# 1DPong_FootController.net
KiCad netlist of a schematic drawn in EAGLE
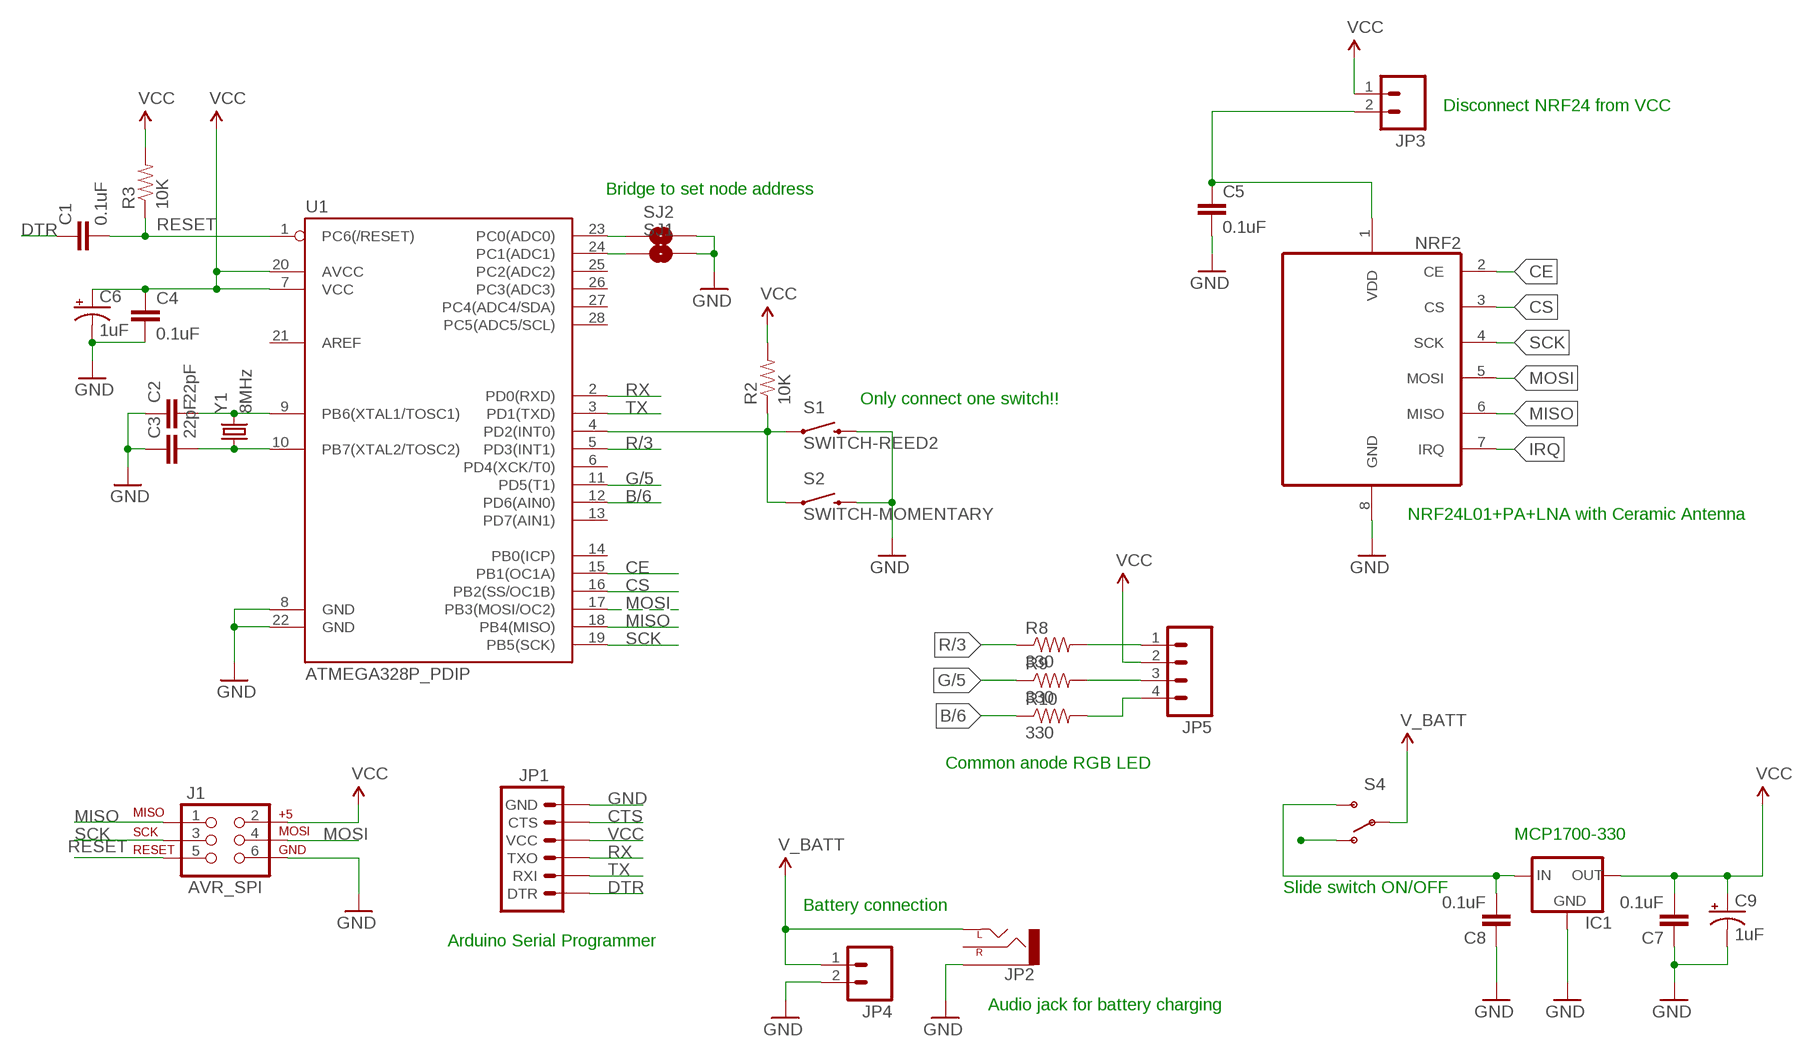
[diagram p0: schematic, sheet 1]

(export (version "E")
  (design (tool "Eeschema 10.0.6"))
  (components
    (comp (ref "C1")
      (value "0.1uF")
      (footprint "eagle-import:CAP-PTH-SMALL")
      (libsource (lib "eagle-import") (part "CAPPTH"))
    )
    (comp (ref "C2")
      (value "22pF")
      (footprint "eagle-import:CAP-PTH-SMALL")
      (libsource (lib "eagle-import") (part "CAPPTH"))
    )
    (comp (ref "C3")
      (value "22pF")
      (footprint "eagle-import:CAP-PTH-SMALL")
      (libsource (lib "eagle-import") (part "CAPPTH"))
    )
    (comp (ref "C4")
      (value "0.1uF")
      (footprint "eagle-import:CAP-PTH-SMALL")
      (libsource (lib "eagle-import") (part "CAPPTH"))
    )
    (comp (ref "C5")
      (value "0.1uF")
      (footprint "eagle-import:CAP-PTH-SMALL")
      (libsource (lib "eagle-import") (part "CAPPTH"))
    )
    (comp (ref "C6")
      (value "1uF")
      (footprint "eagle-import:CPOL-RADIAL-10UF-25V")
      (libsource (lib "eagle-import") (part "CAP_POLPTH2"))
    )
    (comp (ref "C7")
      (value "0.1uF")
      (footprint "eagle-import:CAP-PTH-SMALL")
      (libsource (lib "eagle-import") (part "CAPPTH"))
    )
    (comp (ref "C8")
      (value "0.1uF")
      (footprint "eagle-import:CAP-PTH-SMALL")
      (libsource (lib "eagle-import") (part "CAPPTH"))
    )
    (comp (ref "C9")
      (value "1uF")
      (footprint "eagle-import:CPOL-RADIAL-10UF-25V")
      (libsource (lib "eagle-import") (part "CAP_POLPTH2"))
    )
    (comp (ref "IC1")
      (value "V_REG_78XXTO-92_UNTESTED")
      (footprint "eagle-import:TO-92")
      (libsource (lib "eagle-import") (part "V_REG_78XXTO-92_UNTESTED"))
    )
    (comp (ref "J1")
      (value "AVR_SPI")
      (footprint "eagle-import:2X3")
      (libsource (lib "eagle-import") (part "AVR_SPI_PRG_6PTH"))
    )
    (comp (ref "JP1")
      (value "ARDUINO_SERIAL_PROGRAMPTH")
      (footprint "eagle-import:1X06")
      (libsource (lib "eagle-import") (part "ARDUINO_SERIAL_PROGRAMPTH"))
    )
    (comp (ref "JP2")
      (value "AUDIO-JACKPTH")
      (footprint "eagle-import:AUDIO-JACK")
      (libsource (lib "eagle-import") (part "AUDIO-JACKPTH"))
    )
    (comp (ref "JP3")
      (value "M02PTH")
      (footprint "eagle-import:1X02")
      (libsource (lib "eagle-import") (part "M02PTH"))
    )
    (comp (ref "JP4")
      (value "M02PTH")
      (footprint "eagle-import:1X02")
      (libsource (lib "eagle-import") (part "M02PTH"))
    )
    (comp (ref "JP5")
      (value "M04PTH")
      (footprint "eagle-import:1X04")
      (libsource (lib "eagle-import") (part "M04PTH"))
    )
    (comp (ref "NRF2")
      (value "NRF24L01_SOIC")
      (footprint "eagle-import:NRF24L01_SOIC")
      (libsource (lib "eagle-import") (part "NRF24L01_SOIC"))
    )
    (comp (ref "R2")
      (value "10K")
      (footprint "eagle-import:1206")
      (libsource (lib "eagle-import") (part "RESISTOR1206"))
    )
    (comp (ref "R3")
      (value "10K")
      (footprint "eagle-import:1206")
      (libsource (lib "eagle-import") (part "RESISTOR1206"))
    )
    (comp (ref "R8")
      (value "330")
      (footprint "eagle-import:1206")
      (libsource (lib "eagle-import") (part "RESISTOR1206"))
    )
    (comp (ref "R9")
      (value "330")
      (footprint "eagle-import:1206")
      (libsource (lib "eagle-import") (part "RESISTOR1206"))
    )
    (comp (ref "R10")
      (value "330")
      (footprint "eagle-import:1206")
      (libsource (lib "eagle-import") (part "RESISTOR1206"))
    )
    (comp (ref "S1")
      (value "SWITCH-REED2")
      (footprint "eagle-import:REED_SWITCH_PLASTIC")
      (libsource (lib "eagle-import") (part "SWITCH-MOMENTARY-2PTH_REED2"))
    )
    (comp (ref "S2")
      (value "SWITCH-MOMENTARY")
      (footprint "eagle-import:TACTILE-PTH")
      (libsource (lib "eagle-import") (part "SWITCH-MOMENTARY-2PTH"))
    )
    (comp (ref "S4")
      (value "SWITCH-SPDT-SMD-A")
      (footprint "eagle-import:SWITCH-SPST-SMD-A")
      (libsource (lib "eagle-import") (part "SWITCH-SPDT-SMD-A"))
    )
    (comp (ref "SJ1")
      (value "JUMPER-PAD-2-NOYES_SILK")
      (footprint "eagle-import:PAD-JUMPER-2-NO_YES_SILK")
      (libsource (lib "eagle-import") (part "JUMPER-PAD-2-NOYES_SILK"))
    )
    (comp (ref "SJ2")
      (value "JUMPER-PAD-2-NOYES_SILK")
      (footprint "eagle-import:PAD-JUMPER-2-NO_YES_SILK")
      (libsource (lib "eagle-import") (part "JUMPER-PAD-2-NOYES_SILK"))
    )
    (comp (ref "U1")
      (value "ATMEGA328P_PDIP")
      (footprint "eagle-import:DIL28-3")
      (libsource (lib "eagle-import") (part "ATMEGA328P_PDIP"))
    )
    (comp (ref "Y1")
      (value "8MHz")
      (footprint "eagle-import:HC49US")
      (libsource (lib "eagle-import") (part "CRYSTALHC49US"))
    )
  )
  (nets
    (net (code "1") (name "/CTS") (class "Default")
      (node (ref "JP1") (pin "CTS") (pinfunction "CTS_CTS") (pintype "passive"))
    )
    (net (code "2") (name "/DTR") (class "Default")
      (node (ref "C1") (pin "1") (pinfunction "1_1") (pintype "passive"))
      (node (ref "JP1") (pin "DTR") (pinfunction "DTR_DTR") (pintype "passive"))
    )
    (net (code "3") (name "/RESET") (class "Default")
      (node (ref "C1") (pin "2") (pinfunction "2_2") (pintype "passive"))
      (node (ref "J1") (pin "5") (pinfunction "5_5") (pintype "passive"))
      (node (ref "R3") (pin "1") (pinfunction "1_1") (pintype "passive"))
      (node (ref "U1") (pin "1") (pinfunction "PC6(/RESET)_1") (pintype "bidirectional"))
    )
    (net (code "4") (name "/RX") (class "Default")
      (node (ref "JP1") (pin "TXO") (pinfunction "TXO_TXO") (pintype "passive"))
      (node (ref "U1") (pin "2") (pinfunction "PD0(RXD)_2") (pintype "bidirectional"))
    )
    (net (code "5") (name "/TX") (class "Default")
      (node (ref "JP1") (pin "RXI") (pinfunction "RXI_RXI") (pintype "passive"))
      (node (ref "U1") (pin "3") (pinfunction "PD1(TXD)_3") (pintype "bidirectional"))
    )
    (net (code "6") (name "B{slash}6") (class "Default")
      (node (ref "R10") (pin "1") (pinfunction "1_1") (pintype "passive"))
      (node (ref "U1") (pin "12") (pinfunction "PD6(AIN0)_12") (pintype "bidirectional"))
    )
    (net (code "7") (name "CE") (class "Default")
      (node (ref "NRF2") (pin "2") (pinfunction "CE_2") (pintype "bidirectional"))
      (node (ref "U1") (pin "15") (pinfunction "PB1(OC1A)_15") (pintype "bidirectional"))
    )
    (net (code "8") (name "CS") (class "Default")
      (node (ref "NRF2") (pin "3") (pinfunction "CS_3") (pintype "bidirectional"))
      (node (ref "U1") (pin "16") (pinfunction "PB2(SS/OC1B)_16") (pintype "bidirectional"))
    )
    (net (code "9") (name "GND") (class "Default")
      (node (ref "C2") (pin "1") (pinfunction "1_1") (pintype "passive"))
      (node (ref "C3") (pin "1") (pinfunction "1_1") (pintype "passive"))
      (node (ref "C4") (pin "2") (pinfunction "2_2") (pintype "passive"))
      (node (ref "C5") (pin "2") (pinfunction "2_2") (pintype "passive"))
      (node (ref "C6") (pin "2") (pinfunction "-_2") (pintype "passive"))
      (node (ref "C7") (pin "1") (pinfunction "1_1") (pintype "passive"))
      (node (ref "C8") (pin "1") (pinfunction "1_1") (pintype "passive"))
      (node (ref "C9") (pin "2") (pinfunction "-_2") (pintype "passive"))
      (node (ref "IC1") (pin "1") (pinfunction "GND_1") (pintype "input"))
      (node (ref "J1") (pin "6") (pinfunction "6_6") (pintype "passive"))
      (node (ref "JP1") (pin "GND") (pinfunction "GND_GND") (pintype "passive"))
      (node (ref "JP2") (pin "SLEEVE") (pinfunction "SLEEVE_SLEEVE") (pintype "bidirectional"))
      (node (ref "JP4") (pin "2") (pinfunction "2_2") (pintype "passive"))
      (node (ref "NRF2") (pin "8") (pinfunction "GND_8") (pintype "bidirectional"))
      (node (ref "S1") (pin "P$2") (pinfunction "2_P$2") (pintype "passive"))
      (node (ref "S2") (pin "3") (pinfunction "2_3") (pintype "passive"))
      (node (ref "SJ1") (pin "2") (pinfunction "2_2") (pintype "passive"))
      (node (ref "SJ2") (pin "2") (pinfunction "2_2") (pintype "passive"))
      (node (ref "U1") (pin "22") (pinfunction "GND_22") (pintype "bidirectional"))
      (node (ref "U1") (pin "8") (pinfunction "GND_8") (pintype "bidirectional"))
    )
    (net (code "10") (name "G{slash}5") (class "Default")
      (node (ref "R9") (pin "1") (pinfunction "1_1") (pintype "passive"))
      (node (ref "U1") (pin "11") (pinfunction "PD5(T1)_11") (pintype "bidirectional"))
    )
    (net (code "11") (name "IRQ") (class "Default")
      (node (ref "NRF2") (pin "7") (pinfunction "IRQ_7") (pintype "input"))
    )
    (net (code "12") (name "MISO") (class "Default")
      (node (ref "J1") (pin "1") (pinfunction "1_1") (pintype "passive"))
      (node (ref "NRF2") (pin "6") (pinfunction "MISO_6") (pintype "input"))
      (node (ref "U1") (pin "18") (pinfunction "PB4(MISO)_18") (pintype "bidirectional"))
    )
    (net (code "13") (name "MOSI") (class "Default")
      (node (ref "J1") (pin "4") (pinfunction "4_4") (pintype "passive"))
      (node (ref "NRF2") (pin "5") (pinfunction "MOSI_5") (pintype "bidirectional"))
      (node (ref "U1") (pin "17") (pinfunction "PB3(MOSI/OC2)_17") (pintype "bidirectional"))
    )
    (net (code "14") (name "Net-(IC1-IN)") (class "Default")
      (node (ref "C8") (pin "2") (pinfunction "2_2") (pintype "passive"))
      (node (ref "IC1") (pin "2") (pinfunction "IN_2") (pintype "input"))
      (node (ref "S4") (pin "3") (pinfunction "S_3") (pintype "passive"))
    )
    (net (code "15") (name "Net-(JP5-Pad1)") (class "Default")
      (node (ref "JP5") (pin "1") (pinfunction "1_1") (pintype "passive"))
      (node (ref "R8") (pin "2") (pinfunction "2_2") (pintype "passive"))
    )
    (net (code "16") (name "Net-(JP5-Pad3)") (class "Default")
      (node (ref "JP5") (pin "3") (pinfunction "3_3") (pintype "passive"))
      (node (ref "R9") (pin "2") (pinfunction "2_2") (pintype "passive"))
    )
    (net (code "17") (name "Net-(JP5-Pad4)") (class "Default")
      (node (ref "JP5") (pin "4") (pinfunction "4_4") (pintype "passive"))
      (node (ref "R10") (pin "2") (pinfunction "2_2") (pintype "passive"))
    )
    (net (code "18") (name "Net-(NRF2-VDD)") (class "Default")
      (node (ref "C5") (pin "1") (pinfunction "1_1") (pintype "passive"))
      (node (ref "JP3") (pin "2") (pinfunction "2_2") (pintype "passive"))
      (node (ref "NRF2") (pin "1") (pinfunction "VDD_1") (pintype "bidirectional"))
    )
    (net (code "19") (name "Net-(S1-1)") (class "Default")
      (node (ref "R2") (pin "1") (pinfunction "1_1") (pintype "passive"))
      (node (ref "S1") (pin "P$1") (pinfunction "1_P$1") (pintype "passive"))
      (node (ref "S2") (pin "1") (pinfunction "1_1") (pintype "passive"))
      (node (ref "U1") (pin "4") (pinfunction "PD2(INT0)_4") (pintype "bidirectional"))
    )
    (net (code "20") (name "Net-(U1-PB6(XTAL1{slash}TOSC1))") (class "Default")
      (node (ref "C2") (pin "2") (pinfunction "2_2") (pintype "passive"))
      (node (ref "U1") (pin "9") (pinfunction "PB6(XTAL1/TOSC1)_9") (pintype "bidirectional"))
      (node (ref "Y1") (pin "2") (pinfunction "2_2") (pintype "passive"))
    )
    (net (code "21") (name "Net-(U1-PB7(XTAL2{slash}TOSC2))") (class "Default")
      (node (ref "C3") (pin "2") (pinfunction "2_2") (pintype "passive"))
      (node (ref "U1") (pin "10") (pinfunction "PB7(XTAL2/TOSC2)_10") (pintype "bidirectional"))
      (node (ref "Y1") (pin "1") (pinfunction "1_1") (pintype "passive"))
    )
    (net (code "22") (name "Net-(U1-PC0(ADC0))") (class "Default")
      (node (ref "SJ2") (pin "1") (pinfunction "1_1") (pintype "passive"))
      (node (ref "U1") (pin "23") (pinfunction "PC0(ADC0)_23") (pintype "bidirectional"))
    )
    (net (code "23") (name "Net-(U1-PC1(ADC1))") (class "Default")
      (node (ref "SJ1") (pin "1") (pinfunction "1_1") (pintype "passive"))
      (node (ref "U1") (pin "24") (pinfunction "PC1(ADC1)_24") (pintype "bidirectional"))
    )
    (net (code "24") (name "R{slash}3") (class "Default")
      (node (ref "R8") (pin "1") (pinfunction "1_1") (pintype "passive"))
      (node (ref "U1") (pin "5") (pinfunction "PD3(INT1)_5") (pintype "bidirectional"))
    )
    (net (code "25") (name "SCK") (class "Default")
      (node (ref "J1") (pin "3") (pinfunction "3_3") (pintype "passive"))
      (node (ref "NRF2") (pin "4") (pinfunction "SCK_4") (pintype "bidirectional"))
      (node (ref "U1") (pin "19") (pinfunction "PB5(SCK)_19") (pintype "bidirectional"))
    )
    (net (code "26") (name "VCC") (class "Default")
      (node (ref "C4") (pin "1") (pinfunction "1_1") (pintype "passive"))
      (node (ref "C6") (pin "1") (pinfunction "+_1") (pintype "passive"))
      (node (ref "C7") (pin "2") (pinfunction "2_2") (pintype "passive"))
      (node (ref "C9") (pin "1") (pinfunction "+_1") (pintype "passive"))
      (node (ref "IC1") (pin "3") (pinfunction "OUT_3") (pintype "output"))
      (node (ref "J1") (pin "2") (pinfunction "2_2") (pintype "passive"))
      (node (ref "JP1") (pin "VCC") (pinfunction "VCC_VCC") (pintype "passive"))
      (node (ref "JP3") (pin "1") (pinfunction "1_1") (pintype "passive"))
      (node (ref "JP5") (pin "2") (pinfunction "2_2") (pintype "passive"))
      (node (ref "R2") (pin "2") (pinfunction "2_2") (pintype "passive"))
      (node (ref "R3") (pin "2") (pinfunction "2_2") (pintype "passive"))
      (node (ref "U1") (pin "20") (pinfunction "AVCC_20") (pintype "bidirectional"))
      (node (ref "U1") (pin "7") (pinfunction "VCC_7") (pintype "bidirectional"))
    )
    (net (code "27") (name "V_BATT") (class "Default")
      (node (ref "JP2") (pin "TIP") (pinfunction "LEFT_TIP") (pintype "bidirectional"))
      (node (ref "JP4") (pin "1") (pinfunction "1_1") (pintype "passive"))
      (node (ref "S4") (pin "2") (pinfunction "P_2") (pintype "passive"))
    )
    (net (code "28") (name "unconnected-(JP2-RIGHT-PadRING)") (class "Default")
      (node (ref "JP2") (pin "RING") (pinfunction "RIGHT_RING") (pintype "bidirectional"))
    )
    (net (code "29") (name "unconnected-(S4-O-Pad1)") (class "Default")
      (node (ref "S4") (pin "1") (pinfunction "O_1") (pintype "passive"))
    )
    (net (code "30") (name "unconnected-(U1-AREF-Pad21)") (class "Default")
      (node (ref "U1") (pin "21") (pinfunction "AREF_21") (pintype "bidirectional"))
    )
    (net (code "31") (name "unconnected-(U1-PB0(ICP)-Pad14)") (class "Default")
      (node (ref "U1") (pin "14") (pinfunction "PB0(ICP)_14") (pintype "bidirectional"))
    )
    (net (code "32") (name "unconnected-(U1-PC2(ADC2)-Pad25)") (class "Default")
      (node (ref "U1") (pin "25") (pinfunction "PC2(ADC2)_25") (pintype "bidirectional"))
    )
    (net (code "33") (name "unconnected-(U1-PC3(ADC3)-Pad26)") (class "Default")
      (node (ref "U1") (pin "26") (pinfunction "PC3(ADC3)_26") (pintype "bidirectional"))
    )
    (net (code "34") (name "unconnected-(U1-PC4(ADC4{slash}SDA)-Pad27)") (class "Default")
      (node (ref "U1") (pin "27") (pinfunction "PC4(ADC4/SDA)_27") (pintype "bidirectional"))
    )
    (net (code "35") (name "unconnected-(U1-PC5(ADC5{slash}SCL)-Pad28)") (class "Default")
      (node (ref "U1") (pin "28") (pinfunction "PC5(ADC5/SCL)_28") (pintype "bidirectional"))
    )
    (net (code "36") (name "unconnected-(U1-PD4(XCK{slash}T0)-Pad6)") (class "Default")
      (node (ref "U1") (pin "6") (pinfunction "PD4(XCK/T0)_6") (pintype "bidirectional"))
    )
    (net (code "37") (name "unconnected-(U1-PD7(AIN1)-Pad13)") (class "Default")
      (node (ref "U1") (pin "13") (pinfunction "PD7(AIN1)_13") (pintype "bidirectional"))
    )
  )
)
